# UART.net
KiCad netlist of a schematic drawn in Altium Designer
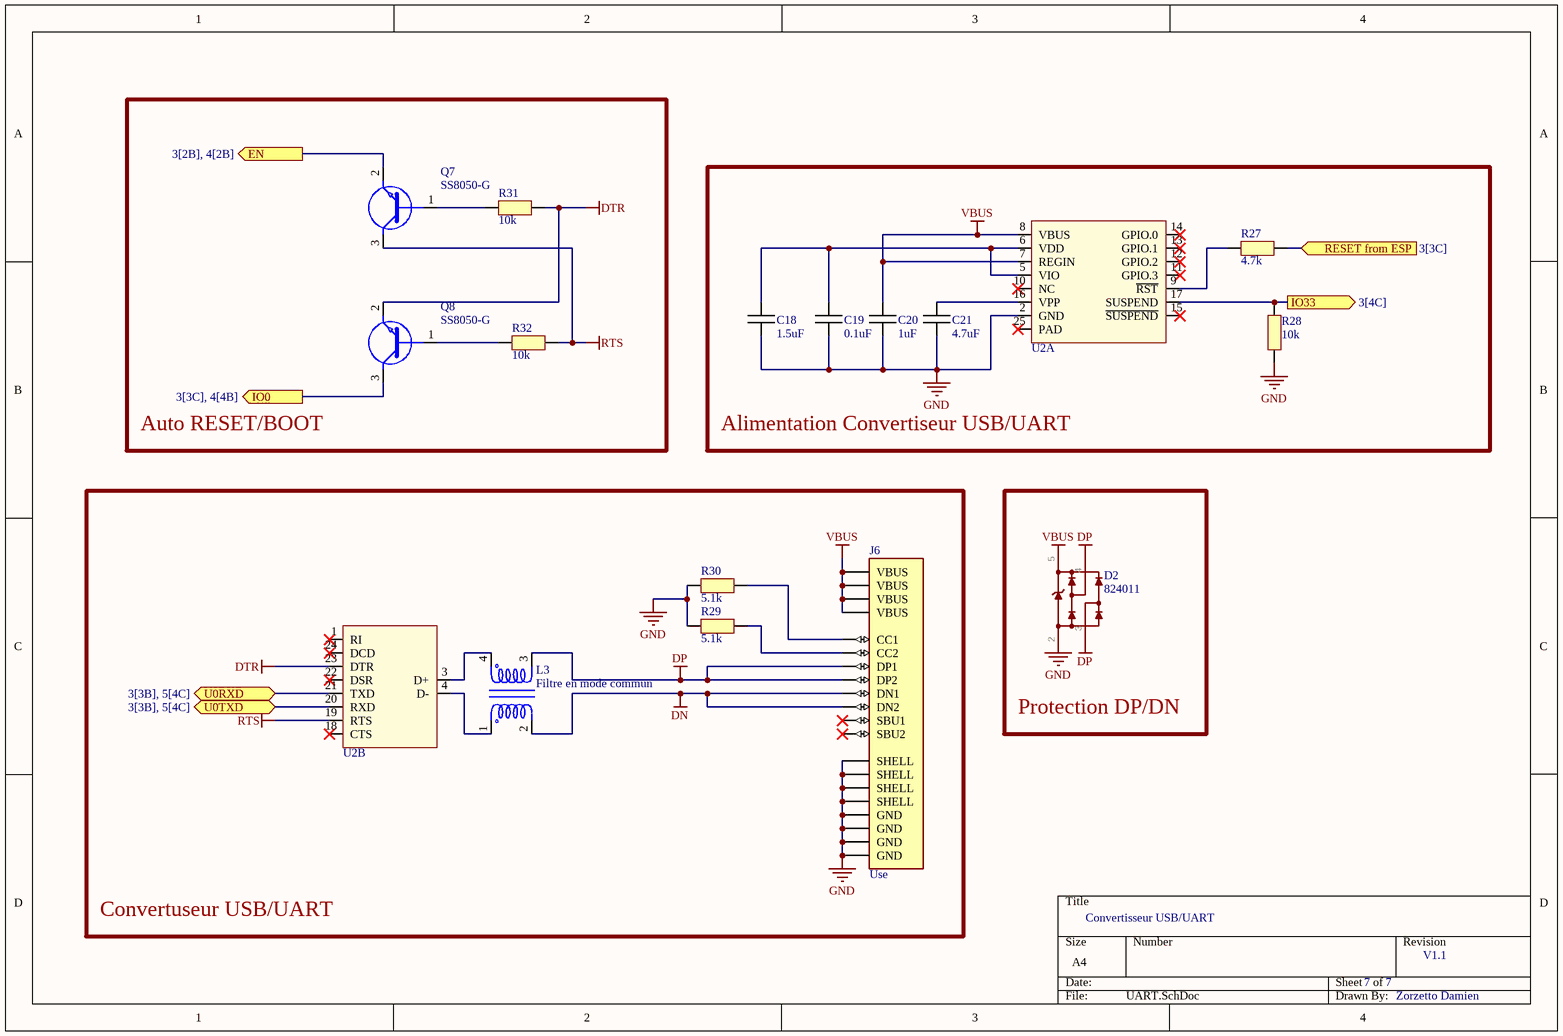
[diagram p0: UART.SchDoc]

(export (version "E")
  (design (tool "Eeschema 10.0.6"))
  (components
    (comp (ref "C18")
      (value "1.5uF")
      (footprint "CAPC1005X06N")
      (libsource (lib "SCHLibrary") (part "Capacitor"))
    )
    (comp (ref "C19")
      (value "0.1uF")
      (footprint "CAPC1005X06N")
      (libsource (lib "SCHLibrary") (part "Capacitor"))
    )
    (comp (ref "C20")
      (value "1uF")
      (footprint "CAPC1005X06N")
      (libsource (lib "SCHLibrary") (part "Capacitor"))
    )
    (comp (ref "C21")
      (value "4.7uF")
      (footprint "CAPC1005X06N")
      (libsource (lib "SCHLibrary") (part "Capacitor"))
    )
    (comp (ref "D2") (value "824011") (footprint "824011") (libsource (lib "SCHLibrary") (part "824011")))
    (comp (ref "J6")
      (value "Use")
      (footprint "USB4085-GF-A")
      (description "Connecteurs USB USB Type C, 2.0, Rec, TH , G/F, RA , Top Mnt, T & R")
      (libsource (lib "SCHLibrary") (part "USB4085-GF-A"))
    )
    (comp (ref "L3")
      (value "Filtre en mode commun")
      (footprint "744232090")
      (description "Bobines / filtres en mode commun WE-CNSW 1206 370mA 90Ohm 100MHz AECQ200")
      (libsource (lib "SCHLibrary") (part "744232090"))
    )
    (comp (ref "Q7")
      (value "SS8050-G")
      (footprint "SS8050-G")
      (description "Bipolar Transistors - BJT NPN TRANSISTOR 1.5A 40V")
      (libsource (lib "SCHLibrary") (part "SS8050-G"))
    )
    (comp (ref "Q8")
      (value "SS8050-G")
      (footprint "SS8050-G")
      (description "Bipolar Transistors - BJT NPN TRANSISTOR 1.5A 40V")
      (libsource (lib "SCHLibrary") (part "SS8050-G"))
    )
    (comp (ref "R27")
      (value "4.7k")
      (footprint "RESC1005X06N")
      (libsource (lib "SCHLibrary") (part "Resistor"))
    )
    (comp (ref "R28") (value "10k") (footprint "RESC1005X06N") (libsource (lib "") (part "Resistor_1")))
    (comp (ref "R29")
      (value "5.1k")
      (footprint "RESC1005X06N")
      (libsource (lib "SCHLibrary") (part "Resistor"))
    )
    (comp (ref "R30")
      (value "5.1k")
      (footprint "RESC1005X06N")
      (libsource (lib "SCHLibrary") (part "Resistor"))
    )
    (comp (ref "R31")
      (value "10k")
      (footprint "RESC1005X06N")
      (libsource (lib "SCHLibrary") (part "Resistor"))
    )
    (comp (ref "R32")
      (value "10k")
      (footprint "RESC1005X06N")
      (libsource (lib "SCHLibrary") (part "Resistor"))
    )
    (comp (ref "U2")
      (value "CP2104-F03-GM")
      (footprint "PQFN50P400X400X80_HS-25N")
      (description "USB Bridge, USB to UART USB 2.0 UART Interface 24-QFN (4x4)")
      (libsource (lib "SCHLibrary") (part "USBBridge"))
    )
  )
  (nets
    (net (code "1") (name "/EN") (class "Default")
      (node (ref "Q7") (pin "2") (pinfunction "E_2") (pintype "passive"))
    )
    (net (code "2") (name "/IO0") (class "Default")
      (node (ref "Q8") (pin "3") (pinfunction "C_3") (pintype "passive"))
    )
    (net (code "3") (name "/IO33") (class "Default")
      (node (ref "R28") (pin "1") (pinfunction "1_1") (pintype "passive"))
      (node (ref "U2") (pin "17") (pinfunction "SUSPEND_17") (pintype "passive"))
    )
    (net (code "4") (name "/RESET from ESP") (class "Default")
      (node (ref "R27") (pin "1") (pinfunction "1_1") (pintype "passive"))
    )
    (net (code "5") (name "/U0RXD") (class "Default")
      (node (ref "U2") (pin "21") (pinfunction "TXD_21") (pintype "passive"))
    )
    (net (code "6") (name "/U0TXD") (class "Default")
      (node (ref "U2") (pin "20") (pinfunction "RXD_20") (pintype "passive"))
    )
    (net (code "7") (name "DN") (class "Default")
      (node (ref "J6") (pin "A7") (pinfunction "DN1_A7") (pintype "bidirectional"))
      (node (ref "J6") (pin "B7") (pinfunction "DN2_B7") (pintype "bidirectional"))
      (node (ref "L3") (pin "2") (pinfunction "2_2") (pintype "passive"))
    )
    (net (code "8") (name "DP") (class "Default")
      (node (ref "D2") (pin "3") (pinfunction "1_3") (pintype "passive"))
      (node (ref "D2") (pin "4") (pinfunction "2_4") (pintype "passive"))
      (node (ref "J6") (pin "A6") (pinfunction "DP1_A6") (pintype "bidirectional"))
      (node (ref "J6") (pin "B6") (pinfunction "DP2_B6") (pintype "bidirectional"))
      (node (ref "L3") (pin "3") (pinfunction "3_3") (pintype "passive"))
    )
    (net (code "9") (name "DTR") (class "Default")
      (node (ref "Q8") (pin "2") (pinfunction "E_2") (pintype "passive"))
      (node (ref "R31") (pin "1") (pinfunction "1_1") (pintype "passive"))
      (node (ref "U2") (pin "23") (pinfunction "DTR_23") (pintype "passive"))
    )
    (net (code "10") (name "GND") (class "Default")
      (node (ref "C18") (pin "2") (pinfunction "2_2") (pintype "passive"))
      (node (ref "C19") (pin "2") (pinfunction "2_2") (pintype "passive"))
      (node (ref "C20") (pin "2") (pinfunction "2_2") (pintype "passive"))
      (node (ref "C21") (pin "2") (pinfunction "2_2") (pintype "passive"))
      (node (ref "D2") (pin "2") (pinfunction "GND_2") (pintype "power_in"))
      (node (ref "J6") (pin "A1") (pinfunction "GND_A1") (pintype "power_in"))
      (node (ref "J6") (pin "A12") (pinfunction "GND_A12") (pintype "power_in"))
      (node (ref "J6") (pin "B1") (pinfunction "GND_B1") (pintype "power_in"))
      (node (ref "J6") (pin "B12") (pinfunction "GND_B12") (pintype "power_in"))
      (node (ref "J6") (pin "S1") (pinfunction "SHELL_S1") (pintype "passive"))
      (node (ref "J6") (pin "S2") (pinfunction "SHELL_S2") (pintype "passive"))
      (node (ref "J6") (pin "S3") (pinfunction "SHELL_S3") (pintype "passive"))
      (node (ref "J6") (pin "S4") (pinfunction "SHELL_S4") (pintype "passive"))
      (node (ref "R28") (pin "2") (pinfunction "2_2") (pintype "passive"))
      (node (ref "R29") (pin "2") (pinfunction "2_2") (pintype "passive"))
      (node (ref "R30") (pin "2") (pinfunction "2_2") (pintype "passive"))
      (node (ref "U2") (pin "2") (pinfunction "GND_2") (pintype "passive"))
    )
    (net (code "11") (name "Net-(J6-CC1)") (class "Default")
      (node (ref "J6") (pin "A5") (pinfunction "CC1_A5") (pintype "bidirectional"))
      (node (ref "R30") (pin "1") (pinfunction "1_1") (pintype "passive"))
    )
    (net (code "12") (name "Net-(J6-CC2)") (class "Default")
      (node (ref "J6") (pin "B5") (pinfunction "CC2_B5") (pintype "bidirectional"))
      (node (ref "R29") (pin "1") (pinfunction "1_1") (pintype "passive"))
    )
    (net (code "13") (name "Net-(Q7-B)") (class "Default")
      (node (ref "Q7") (pin "1") (pinfunction "B_1") (pintype "passive"))
      (node (ref "R31") (pin "2") (pinfunction "2_2") (pintype "passive"))
    )
    (net (code "14") (name "Net-(Q8-B)") (class "Default")
      (node (ref "Q8") (pin "1") (pinfunction "B_1") (pintype "passive"))
      (node (ref "R32") (pin "2") (pinfunction "2_2") (pintype "passive"))
    )
    (net (code "15") (name "Net-(U2A-VDD)") (class "Default")
      (node (ref "C18") (pin "1") (pinfunction "1_1") (pintype "passive"))
      (node (ref "C19") (pin "1") (pinfunction "1_1") (pintype "passive"))
      (node (ref "U2") (pin "5") (pinfunction "VIO_5") (pintype "passive"))
      (node (ref "U2") (pin "6") (pinfunction "VDD_6") (pintype "passive"))
    )
    (net (code "16") (name "Net-(U2A-VPP)") (class "Default")
      (node (ref "C21") (pin "1") (pinfunction "1_1") (pintype "passive"))
      (node (ref "U2") (pin "16") (pinfunction "VPP_16") (pintype "passive"))
    )
    (net (code "17") (name "Net-(U2A-~{RST})") (class "Default")
      (node (ref "R27") (pin "2") (pinfunction "2_2") (pintype "passive"))
      (node (ref "U2") (pin "9") (pinfunction "~{RST}_9") (pintype "passive"))
    )
    (net (code "18") (name "Net-(U2B-D+)") (class "Default")
      (node (ref "L3") (pin "4") (pinfunction "4_4") (pintype "passive"))
      (node (ref "U2") (pin "3") (pinfunction "D+_3") (pintype "passive"))
    )
    (net (code "19") (name "Net-(U2B-D-)") (class "Default")
      (node (ref "L3") (pin "1") (pinfunction "1_1") (pintype "passive"))
      (node (ref "U2") (pin "4") (pinfunction "D-_4") (pintype "passive"))
    )
    (net (code "20") (name "RTS") (class "Default")
      (node (ref "Q7") (pin "3") (pinfunction "C_3") (pintype "passive"))
      (node (ref "R32") (pin "1") (pinfunction "1_1") (pintype "passive"))
      (node (ref "U2") (pin "19") (pinfunction "RTS_19") (pintype "passive"))
    )
    (net (code "21") (name "VBUS") (class "Default")
      (node (ref "C20") (pin "1") (pinfunction "1_1") (pintype "passive"))
      (node (ref "D2") (pin "5") (pinfunction "VDD_5") (pintype "power_in"))
      (node (ref "J6") (pin "A4") (pinfunction "VBUS_A4") (pintype "power_in"))
      (node (ref "J6") (pin "A9") (pinfunction "VBUS_A9") (pintype "power_in"))
      (node (ref "J6") (pin "B4") (pinfunction "VBUS_B4") (pintype "power_in"))
      (node (ref "J6") (pin "B9") (pinfunction "VBUS_B9") (pintype "power_in"))
      (node (ref "U2") (pin "7") (pinfunction "REGIN_7") (pintype "passive"))
      (node (ref "U2") (pin "8") (pinfunction "VBUS_8") (pintype "passive"))
    )
    (net (code "22") (name "unconnected-(J6-SBU1-PadA8)") (class "Default")
      (node (ref "J6") (pin "A8") (pinfunction "SBU1_A8") (pintype "bidirectional+no_connect"))
    )
    (net (code "23") (name "unconnected-(J6-SBU2-PadB8)") (class "Default")
      (node (ref "J6") (pin "B8") (pinfunction "SBU2_B8") (pintype "bidirectional+no_connect"))
    )
    (net (code "24") (name "unconnected-(U2A-GPIO.0-Pad14)") (class "Default")
      (node (ref "U2") (pin "14") (pinfunction "GPIO.0_14") (pintype "passive+no_connect"))
    )
    (net (code "25") (name "unconnected-(U2A-GPIO.1-Pad13)") (class "Default")
      (node (ref "U2") (pin "13") (pinfunction "GPIO.1_13") (pintype "passive+no_connect"))
    )
    (net (code "26") (name "unconnected-(U2A-GPIO.2-Pad12)") (class "Default")
      (node (ref "U2") (pin "12") (pinfunction "GPIO.2_12") (pintype "passive+no_connect"))
    )
    (net (code "27") (name "unconnected-(U2A-GPIO.3-Pad11)") (class "Default")
      (node (ref "U2") (pin "11") (pinfunction "GPIO.3_11") (pintype "passive+no_connect"))
    )
    (net (code "28") (name "unconnected-(U2A-NC-Pad10)") (class "Default")
      (node (ref "U2") (pin "10") (pinfunction "NC_10") (pintype "passive+no_connect"))
    )
    (net (code "29") (name "unconnected-(U2A-PAD-Pad25)") (class "Default")
      (node (ref "U2") (pin "25") (pinfunction "PAD_25") (pintype "passive+no_connect"))
    )
    (net (code "30") (name "unconnected-(U2A-~{SUSPEND}-Pad15)") (class "Default")
      (node (ref "U2") (pin "15") (pinfunction "~{SUSPEND}_15") (pintype "passive+no_connect"))
    )
    (net (code "31") (name "unconnected-(U2B-CTS-Pad18)") (class "Default")
      (node (ref "U2") (pin "18") (pinfunction "CTS_18") (pintype "passive+no_connect"))
    )
    (net (code "32") (name "unconnected-(U2B-DCD-Pad24)") (class "Default")
      (node (ref "U2") (pin "24") (pinfunction "DCD_24") (pintype "passive+no_connect"))
    )
    (net (code "33") (name "unconnected-(U2B-DSR-Pad22)") (class "Default")
      (node (ref "U2") (pin "22") (pinfunction "DSR_22") (pintype "passive+no_connect"))
    )
    (net (code "34") (name "unconnected-(U2B-RI-Pad1)") (class "Default")
      (node (ref "U2") (pin "1") (pinfunction "RI_1") (pintype "passive+no_connect"))
    )
  )
)
